# labwiz-module_full_breakout.net
KiCad netlist of a schematic drawn in EAGLE
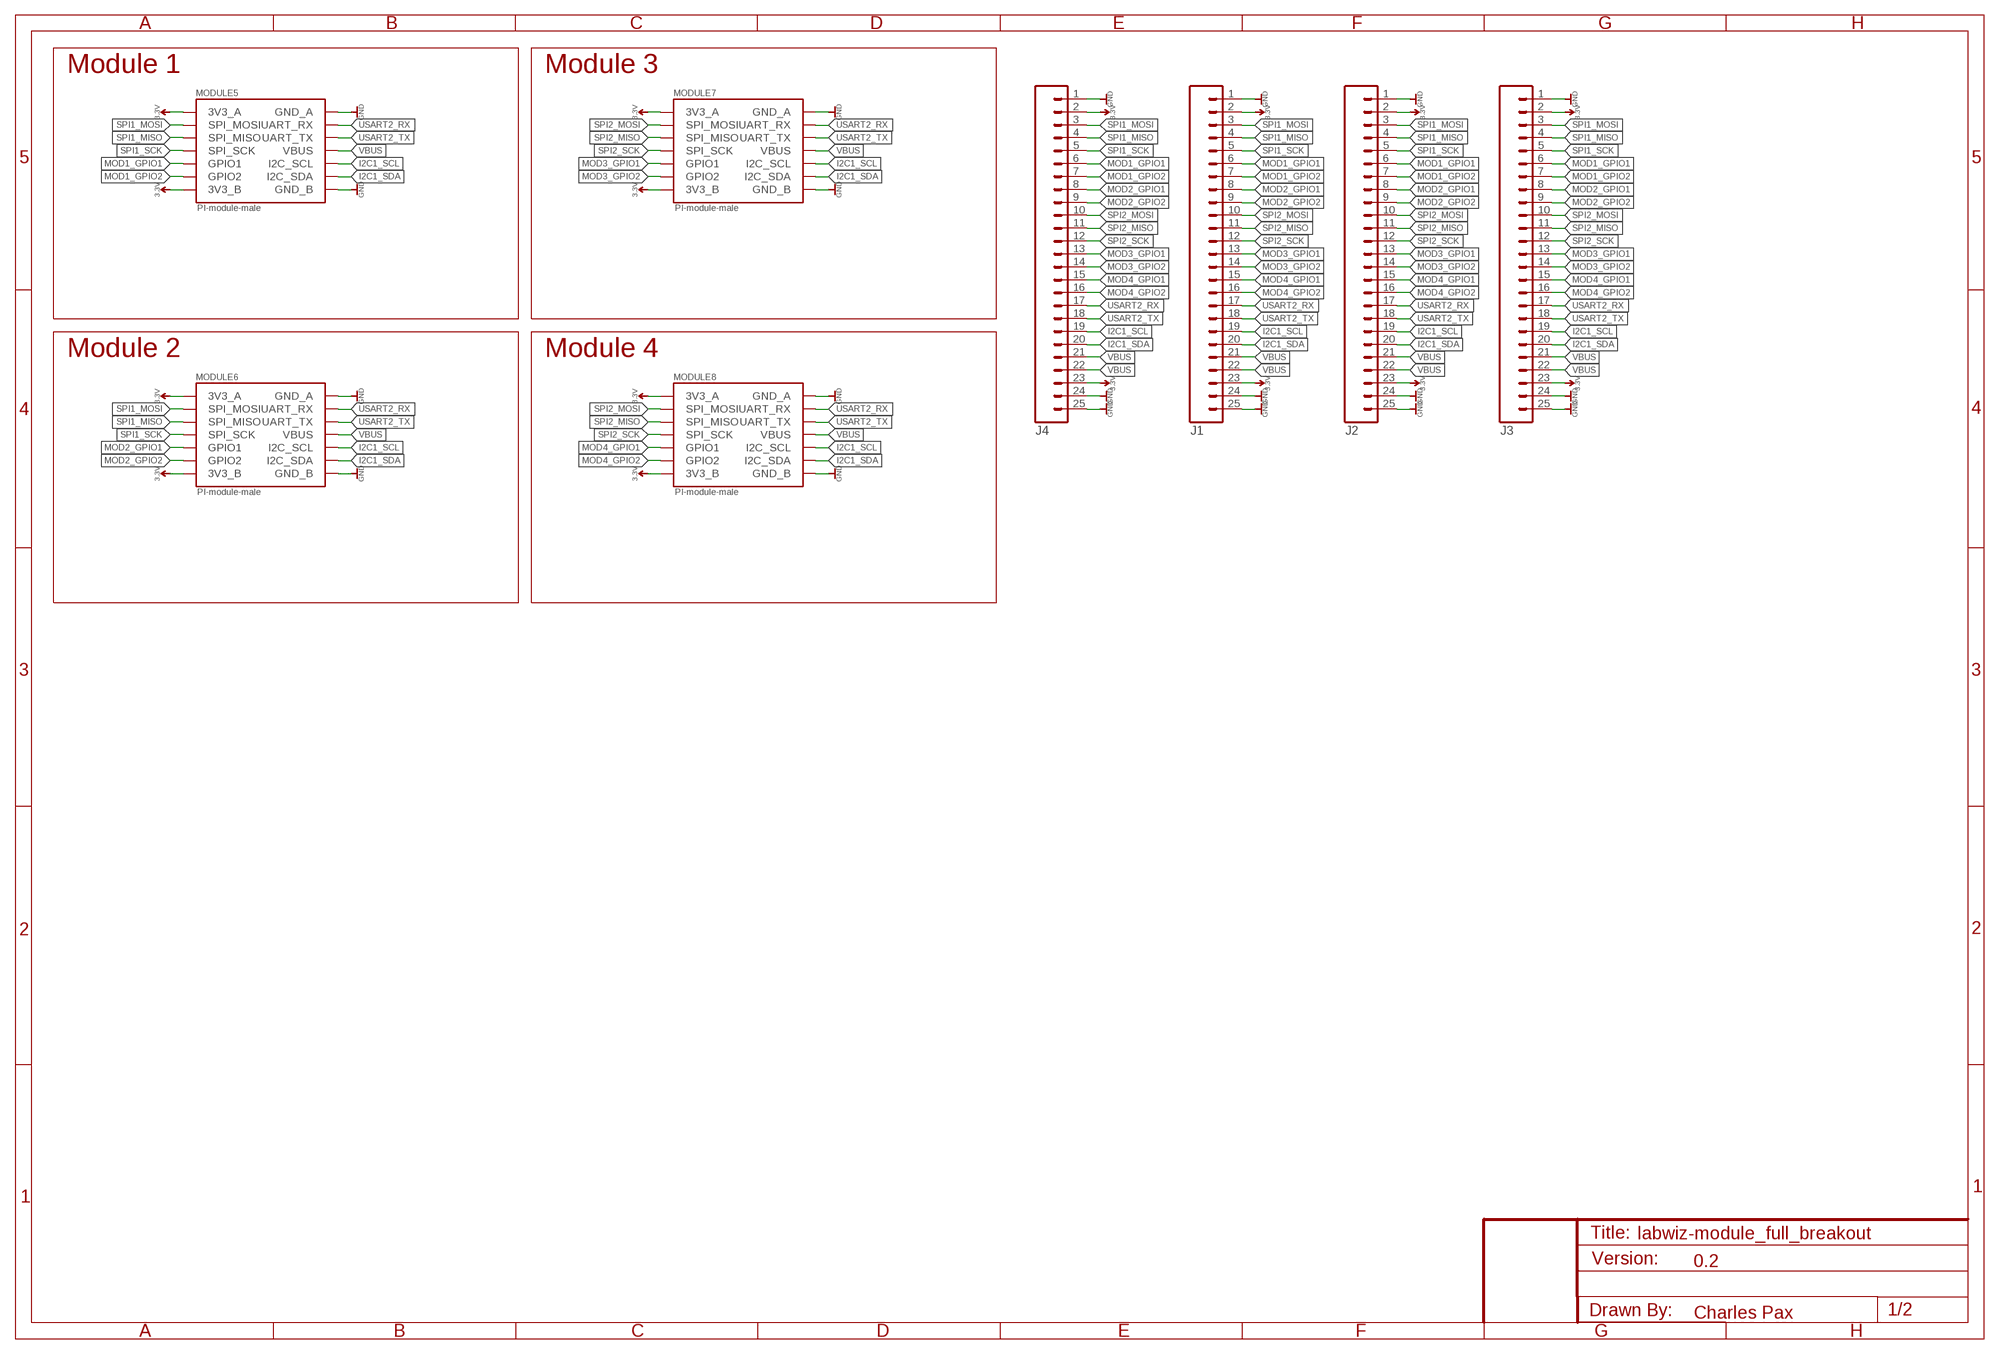
[diagram p0: schematic, sheet 1]

(export (version "E")
  (design (tool "Eeschema 10.0.6"))
  (components
    (comp (ref "J1")
      (value "M25PTH")
      (footprint "eagle-import:1X25")
      (libsource (lib "eagle-import") (part "M25PTH"))
    )
    (comp (ref "J2")
      (value "M25PTH")
      (footprint "eagle-import:1X25")
      (libsource (lib "eagle-import") (part "M25PTH"))
    )
    (comp (ref "J3")
      (value "M25PTH")
      (footprint "eagle-import:1X25")
      (libsource (lib "eagle-import") (part "M25PTH"))
    )
    (comp (ref "J4")
      (value "M25PTH")
      (footprint "eagle-import:1X25")
      (libsource (lib "eagle-import") (part "M25PTH"))
    )
    (comp (ref "MODULE5")
      (value "PI-module-male")
      (footprint "eagle-import:M07X2_2MM_EDGE")
      (fields (field (name "MF") "Pax Instruments") (field (name "MPN") "PIxxxx"))
      (libsource (lib "eagle-import") (part "PAX_MODULE_EDGE_MALE_MODULE"))
    )
    (comp (ref "MODULE6")
      (value "PI-module-male")
      (footprint "eagle-import:M07X2_2MM_EDGE")
      (fields (field (name "MF") "Pax Instruments") (field (name "MPN") "PIxxxx"))
      (libsource (lib "eagle-import") (part "PAX_MODULE_EDGE_MALE_MODULE"))
    )
    (comp (ref "MODULE7")
      (value "PI-module-male")
      (footprint "eagle-import:M07X2_2MM_EDGE")
      (fields (field (name "MF") "Pax Instruments") (field (name "MPN") "PIxxxx"))
      (libsource (lib "eagle-import") (part "PAX_MODULE_EDGE_MALE_MODULE"))
    )
    (comp (ref "MODULE8")
      (value "PI-module-male")
      (footprint "eagle-import:M07X2_2MM_EDGE")
      (fields (field (name "MF") "Pax Instruments") (field (name "MPN") "PIxxxx"))
      (libsource (lib "eagle-import") (part "PAX_MODULE_EDGE_MALE_MODULE"))
    )
  )
  (nets
    (net (code "1") (name "3.3V") (class "Default")
      (node (ref "J1") (pin "2") (pinfunction "2_2") (pintype "passive"))
      (node (ref "J1") (pin "23") (pinfunction "23_23") (pintype "passive"))
      (node (ref "J2") (pin "2") (pinfunction "2_2") (pintype "passive"))
      (node (ref "J2") (pin "23") (pinfunction "23_23") (pintype "passive"))
      (node (ref "J3") (pin "2") (pinfunction "2_2") (pintype "passive"))
      (node (ref "J3") (pin "23") (pinfunction "23_23") (pintype "passive"))
      (node (ref "J4") (pin "2") (pinfunction "2_2") (pintype "passive"))
      (node (ref "J4") (pin "23") (pinfunction "23_23") (pintype "passive"))
      (node (ref "MODULE5") (pin "P$1") (pinfunction "3V3_B_P$1") (pintype "bidirectional"))
      (node (ref "MODULE5") (pin "P$13") (pinfunction "3V3_A_P$13") (pintype "power_in"))
      (node (ref "MODULE6") (pin "P$1") (pinfunction "3V3_B_P$1") (pintype "bidirectional"))
      (node (ref "MODULE6") (pin "P$13") (pinfunction "3V3_A_P$13") (pintype "power_in"))
      (node (ref "MODULE7") (pin "P$1") (pinfunction "3V3_B_P$1") (pintype "bidirectional"))
      (node (ref "MODULE7") (pin "P$13") (pinfunction "3V3_A_P$13") (pintype "power_in"))
      (node (ref "MODULE8") (pin "P$1") (pinfunction "3V3_B_P$1") (pintype "bidirectional"))
      (node (ref "MODULE8") (pin "P$13") (pinfunction "3V3_A_P$13") (pintype "power_in"))
    )
    (net (code "2") (name "GND") (class "Default")
      (node (ref "J1") (pin "1") (pinfunction "1_1") (pintype "passive"))
      (node (ref "J1") (pin "24") (pinfunction "24_24") (pintype "passive"))
      (node (ref "J1") (pin "25") (pinfunction "25_25") (pintype "passive"))
      (node (ref "J2") (pin "1") (pinfunction "1_1") (pintype "passive"))
      (node (ref "J2") (pin "24") (pinfunction "24_24") (pintype "passive"))
      (node (ref "J2") (pin "25") (pinfunction "25_25") (pintype "passive"))
      (node (ref "J3") (pin "1") (pinfunction "1_1") (pintype "passive"))
      (node (ref "J3") (pin "24") (pinfunction "24_24") (pintype "passive"))
      (node (ref "J3") (pin "25") (pinfunction "25_25") (pintype "passive"))
      (node (ref "J4") (pin "1") (pinfunction "1_1") (pintype "passive"))
      (node (ref "J4") (pin "24") (pinfunction "24_24") (pintype "passive"))
      (node (ref "J4") (pin "25") (pinfunction "25_25") (pintype "passive"))
      (node (ref "MODULE5") (pin "P$14") (pinfunction "GND_A_P$14") (pintype "power_in"))
      (node (ref "MODULE5") (pin "P$2") (pinfunction "GND_B_P$2") (pintype "bidirectional"))
      (node (ref "MODULE6") (pin "P$14") (pinfunction "GND_A_P$14") (pintype "power_in"))
      (node (ref "MODULE6") (pin "P$2") (pinfunction "GND_B_P$2") (pintype "bidirectional"))
      (node (ref "MODULE7") (pin "P$14") (pinfunction "GND_A_P$14") (pintype "power_in"))
      (node (ref "MODULE7") (pin "P$2") (pinfunction "GND_B_P$2") (pintype "bidirectional"))
      (node (ref "MODULE8") (pin "P$14") (pinfunction "GND_A_P$14") (pintype "power_in"))
      (node (ref "MODULE8") (pin "P$2") (pinfunction "GND_B_P$2") (pintype "bidirectional"))
    )
    (net (code "3") (name "I2C1_SCL") (class "Default")
      (node (ref "J1") (pin "19") (pinfunction "19_19") (pintype "passive"))
      (node (ref "J2") (pin "19") (pinfunction "19_19") (pintype "passive"))
      (node (ref "J3") (pin "19") (pinfunction "19_19") (pintype "passive"))
      (node (ref "J4") (pin "19") (pinfunction "19_19") (pintype "passive"))
      (node (ref "MODULE5") (pin "P$6") (pinfunction "I2C_SCL_P$6") (pintype "bidirectional"))
      (node (ref "MODULE6") (pin "P$6") (pinfunction "I2C_SCL_P$6") (pintype "bidirectional"))
      (node (ref "MODULE7") (pin "P$6") (pinfunction "I2C_SCL_P$6") (pintype "bidirectional"))
      (node (ref "MODULE8") (pin "P$6") (pinfunction "I2C_SCL_P$6") (pintype "bidirectional"))
    )
    (net (code "4") (name "I2C1_SDA") (class "Default")
      (node (ref "J1") (pin "20") (pinfunction "20_20") (pintype "passive"))
      (node (ref "J2") (pin "20") (pinfunction "20_20") (pintype "passive"))
      (node (ref "J3") (pin "20") (pinfunction "20_20") (pintype "passive"))
      (node (ref "J4") (pin "20") (pinfunction "20_20") (pintype "passive"))
      (node (ref "MODULE5") (pin "P$4") (pinfunction "I2C_SDA_P$4") (pintype "bidirectional"))
      (node (ref "MODULE6") (pin "P$4") (pinfunction "I2C_SDA_P$4") (pintype "bidirectional"))
      (node (ref "MODULE7") (pin "P$4") (pinfunction "I2C_SDA_P$4") (pintype "bidirectional"))
      (node (ref "MODULE8") (pin "P$4") (pinfunction "I2C_SDA_P$4") (pintype "bidirectional"))
    )
    (net (code "5") (name "MOD1_GPIO1") (class "Default")
      (node (ref "J1") (pin "6") (pinfunction "6_6") (pintype "passive"))
      (node (ref "J2") (pin "6") (pinfunction "6_6") (pintype "passive"))
      (node (ref "J3") (pin "6") (pinfunction "6_6") (pintype "passive"))
      (node (ref "J4") (pin "6") (pinfunction "6_6") (pintype "passive"))
      (node (ref "MODULE5") (pin "P$5") (pinfunction "GPIO1_P$5") (pintype "bidirectional"))
    )
    (net (code "6") (name "MOD1_GPIO2") (class "Default")
      (node (ref "J1") (pin "7") (pinfunction "7_7") (pintype "passive"))
      (node (ref "J2") (pin "7") (pinfunction "7_7") (pintype "passive"))
      (node (ref "J3") (pin "7") (pinfunction "7_7") (pintype "passive"))
      (node (ref "J4") (pin "7") (pinfunction "7_7") (pintype "passive"))
      (node (ref "MODULE5") (pin "P$3") (pinfunction "GPIO2_P$3") (pintype "bidirectional"))
    )
    (net (code "7") (name "MOD2_GPIO1") (class "Default")
      (node (ref "J1") (pin "8") (pinfunction "8_8") (pintype "passive"))
      (node (ref "J2") (pin "8") (pinfunction "8_8") (pintype "passive"))
      (node (ref "J3") (pin "8") (pinfunction "8_8") (pintype "passive"))
      (node (ref "J4") (pin "8") (pinfunction "8_8") (pintype "passive"))
      (node (ref "MODULE6") (pin "P$5") (pinfunction "GPIO1_P$5") (pintype "bidirectional"))
    )
    (net (code "8") (name "MOD2_GPIO2") (class "Default")
      (node (ref "J1") (pin "9") (pinfunction "9_9") (pintype "passive"))
      (node (ref "J2") (pin "9") (pinfunction "9_9") (pintype "passive"))
      (node (ref "J3") (pin "9") (pinfunction "9_9") (pintype "passive"))
      (node (ref "J4") (pin "9") (pinfunction "9_9") (pintype "passive"))
      (node (ref "MODULE6") (pin "P$3") (pinfunction "GPIO2_P$3") (pintype "bidirectional"))
    )
    (net (code "9") (name "MOD3_GPIO1") (class "Default")
      (node (ref "J1") (pin "13") (pinfunction "13_13") (pintype "passive"))
      (node (ref "J2") (pin "13") (pinfunction "13_13") (pintype "passive"))
      (node (ref "J3") (pin "13") (pinfunction "13_13") (pintype "passive"))
      (node (ref "J4") (pin "13") (pinfunction "13_13") (pintype "passive"))
      (node (ref "MODULE7") (pin "P$5") (pinfunction "GPIO1_P$5") (pintype "bidirectional"))
    )
    (net (code "10") (name "MOD3_GPIO2") (class "Default")
      (node (ref "J1") (pin "14") (pinfunction "14_14") (pintype "passive"))
      (node (ref "J2") (pin "14") (pinfunction "14_14") (pintype "passive"))
      (node (ref "J3") (pin "14") (pinfunction "14_14") (pintype "passive"))
      (node (ref "J4") (pin "14") (pinfunction "14_14") (pintype "passive"))
      (node (ref "MODULE7") (pin "P$3") (pinfunction "GPIO2_P$3") (pintype "bidirectional"))
    )
    (net (code "11") (name "MOD4_GPIO1") (class "Default")
      (node (ref "J1") (pin "15") (pinfunction "15_15") (pintype "passive"))
      (node (ref "J2") (pin "15") (pinfunction "15_15") (pintype "passive"))
      (node (ref "J3") (pin "15") (pinfunction "15_15") (pintype "passive"))
      (node (ref "J4") (pin "15") (pinfunction "15_15") (pintype "passive"))
      (node (ref "MODULE8") (pin "P$5") (pinfunction "GPIO1_P$5") (pintype "bidirectional"))
    )
    (net (code "12") (name "MOD4_GPIO2") (class "Default")
      (node (ref "J1") (pin "16") (pinfunction "16_16") (pintype "passive"))
      (node (ref "J2") (pin "16") (pinfunction "16_16") (pintype "passive"))
      (node (ref "J3") (pin "16") (pinfunction "16_16") (pintype "passive"))
      (node (ref "J4") (pin "16") (pinfunction "16_16") (pintype "passive"))
      (node (ref "MODULE8") (pin "P$3") (pinfunction "GPIO2_P$3") (pintype "bidirectional"))
    )
    (net (code "13") (name "SPI1_MISO") (class "Default")
      (node (ref "J1") (pin "4") (pinfunction "4_4") (pintype "passive"))
      (node (ref "J2") (pin "4") (pinfunction "4_4") (pintype "passive"))
      (node (ref "J3") (pin "4") (pinfunction "4_4") (pintype "passive"))
      (node (ref "J4") (pin "4") (pinfunction "4_4") (pintype "passive"))
      (node (ref "MODULE5") (pin "P$9") (pinfunction "SPI_MISO_P$9") (pintype "bidirectional"))
      (node (ref "MODULE6") (pin "P$9") (pinfunction "SPI_MISO_P$9") (pintype "bidirectional"))
    )
    (net (code "14") (name "SPI1_MOSI") (class "Default")
      (node (ref "J1") (pin "3") (pinfunction "3_3") (pintype "passive"))
      (node (ref "J2") (pin "3") (pinfunction "3_3") (pintype "passive"))
      (node (ref "J3") (pin "3") (pinfunction "3_3") (pintype "passive"))
      (node (ref "J4") (pin "3") (pinfunction "3_3") (pintype "passive"))
      (node (ref "MODULE5") (pin "P$11") (pinfunction "SPI_MOSI_P$11") (pintype "bidirectional"))
      (node (ref "MODULE6") (pin "P$11") (pinfunction "SPI_MOSI_P$11") (pintype "bidirectional"))
    )
    (net (code "15") (name "SPI1_SCK") (class "Default")
      (node (ref "J1") (pin "5") (pinfunction "5_5") (pintype "passive"))
      (node (ref "J2") (pin "5") (pinfunction "5_5") (pintype "passive"))
      (node (ref "J3") (pin "5") (pinfunction "5_5") (pintype "passive"))
      (node (ref "J4") (pin "5") (pinfunction "5_5") (pintype "passive"))
      (node (ref "MODULE5") (pin "P$7") (pinfunction "SPI_SCK_P$7") (pintype "bidirectional"))
      (node (ref "MODULE6") (pin "P$7") (pinfunction "SPI_SCK_P$7") (pintype "bidirectional"))
    )
    (net (code "16") (name "SPI2_MISO") (class "Default")
      (node (ref "J1") (pin "11") (pinfunction "11_11") (pintype "passive"))
      (node (ref "J2") (pin "11") (pinfunction "11_11") (pintype "passive"))
      (node (ref "J3") (pin "11") (pinfunction "11_11") (pintype "passive"))
      (node (ref "J4") (pin "11") (pinfunction "11_11") (pintype "passive"))
      (node (ref "MODULE7") (pin "P$9") (pinfunction "SPI_MISO_P$9") (pintype "bidirectional"))
      (node (ref "MODULE8") (pin "P$9") (pinfunction "SPI_MISO_P$9") (pintype "bidirectional"))
    )
    (net (code "17") (name "SPI2_MOSI") (class "Default")
      (node (ref "J1") (pin "10") (pinfunction "10_10") (pintype "passive"))
      (node (ref "J2") (pin "10") (pinfunction "10_10") (pintype "passive"))
      (node (ref "J3") (pin "10") (pinfunction "10_10") (pintype "passive"))
      (node (ref "J4") (pin "10") (pinfunction "10_10") (pintype "passive"))
      (node (ref "MODULE7") (pin "P$11") (pinfunction "SPI_MOSI_P$11") (pintype "bidirectional"))
      (node (ref "MODULE8") (pin "P$11") (pinfunction "SPI_MOSI_P$11") (pintype "bidirectional"))
    )
    (net (code "18") (name "SPI2_SCK") (class "Default")
      (node (ref "J1") (pin "12") (pinfunction "12_12") (pintype "passive"))
      (node (ref "J2") (pin "12") (pinfunction "12_12") (pintype "passive"))
      (node (ref "J3") (pin "12") (pinfunction "12_12") (pintype "passive"))
      (node (ref "J4") (pin "12") (pinfunction "12_12") (pintype "passive"))
      (node (ref "MODULE7") (pin "P$7") (pinfunction "SPI_SCK_P$7") (pintype "bidirectional"))
      (node (ref "MODULE8") (pin "P$7") (pinfunction "SPI_SCK_P$7") (pintype "bidirectional"))
    )
    (net (code "19") (name "USART2_RX") (class "Default")
      (node (ref "J1") (pin "17") (pinfunction "17_17") (pintype "passive"))
      (node (ref "J2") (pin "17") (pinfunction "17_17") (pintype "passive"))
      (node (ref "J3") (pin "17") (pinfunction "17_17") (pintype "passive"))
      (node (ref "J4") (pin "17") (pinfunction "17_17") (pintype "passive"))
      (node (ref "MODULE5") (pin "P$12") (pinfunction "UART_RX_P$12") (pintype "bidirectional"))
      (node (ref "MODULE6") (pin "P$12") (pinfunction "UART_RX_P$12") (pintype "bidirectional"))
      (node (ref "MODULE7") (pin "P$12") (pinfunction "UART_RX_P$12") (pintype "bidirectional"))
      (node (ref "MODULE8") (pin "P$12") (pinfunction "UART_RX_P$12") (pintype "bidirectional"))
    )
    (net (code "20") (name "USART2_TX") (class "Default")
      (node (ref "J1") (pin "18") (pinfunction "18_18") (pintype "passive"))
      (node (ref "J2") (pin "18") (pinfunction "18_18") (pintype "passive"))
      (node (ref "J3") (pin "18") (pinfunction "18_18") (pintype "passive"))
      (node (ref "J4") (pin "18") (pinfunction "18_18") (pintype "passive"))
      (node (ref "MODULE5") (pin "P$10") (pinfunction "UART_TX_P$10") (pintype "bidirectional"))
      (node (ref "MODULE6") (pin "P$10") (pinfunction "UART_TX_P$10") (pintype "bidirectional"))
      (node (ref "MODULE7") (pin "P$10") (pinfunction "UART_TX_P$10") (pintype "bidirectional"))
      (node (ref "MODULE8") (pin "P$10") (pinfunction "UART_TX_P$10") (pintype "bidirectional"))
    )
    (net (code "21") (name "VBUS") (class "Default")
      (node (ref "J1") (pin "21") (pinfunction "21_21") (pintype "passive"))
      (node (ref "J1") (pin "22") (pinfunction "22_22") (pintype "passive"))
      (node (ref "J2") (pin "21") (pinfunction "21_21") (pintype "passive"))
      (node (ref "J2") (pin "22") (pinfunction "22_22") (pintype "passive"))
      (node (ref "J3") (pin "21") (pinfunction "21_21") (pintype "passive"))
      (node (ref "J3") (pin "22") (pinfunction "22_22") (pintype "passive"))
      (node (ref "J4") (pin "21") (pinfunction "21_21") (pintype "passive"))
      (node (ref "J4") (pin "22") (pinfunction "22_22") (pintype "passive"))
      (node (ref "MODULE5") (pin "P$8") (pinfunction "VBUS_P$8") (pintype "bidirectional"))
      (node (ref "MODULE6") (pin "P$8") (pinfunction "VBUS_P$8") (pintype "bidirectional"))
      (node (ref "MODULE7") (pin "P$8") (pinfunction "VBUS_P$8") (pintype "bidirectional"))
      (node (ref "MODULE8") (pin "P$8") (pinfunction "VBUS_P$8") (pintype "bidirectional"))
    )
  )
)
